# Battery-management.net
KiCad netlist of a schematic drawn in Altium Designer
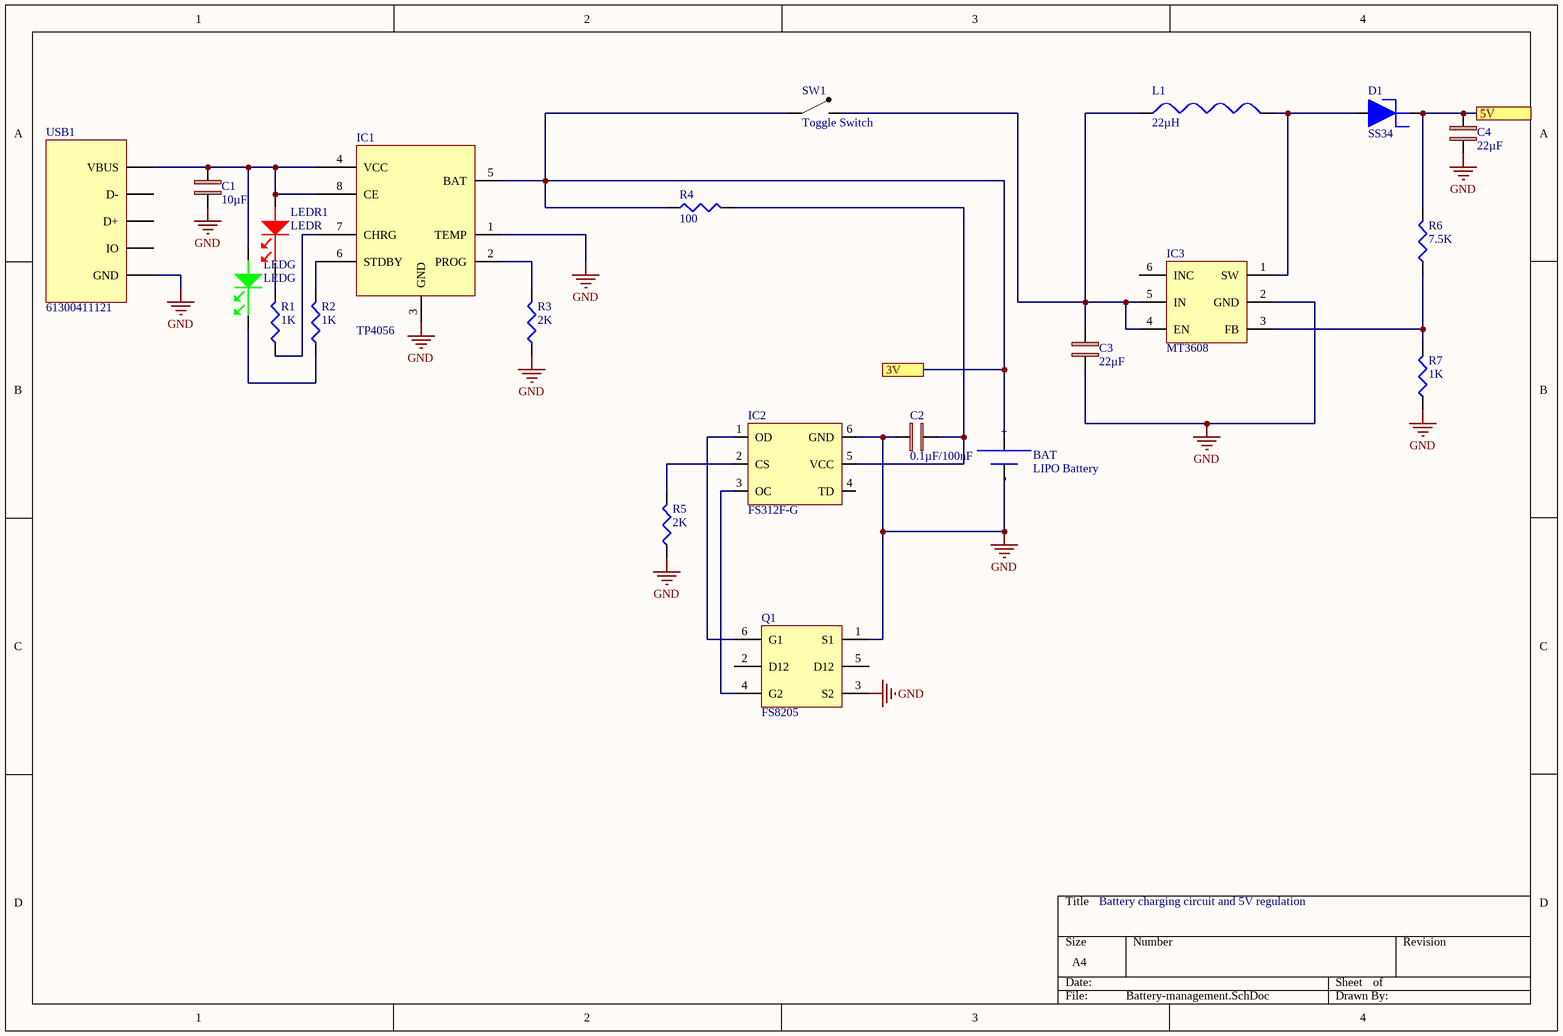
[diagram p0: Battery-management.SchDoc]

(export (version "E")
  (design (tool "Eeschema 10.0.6"))
  (components
    (comp (ref "BAT")
      (value "LIPO Battery")
      (footprint "LIPO battery pads")
      (libsource (lib "Tama_Schlib") (part "103040 LIPO battery"))
    )
    (comp (ref "C1")
      (value "10µF")
      (footprint "ELCO")
      (description "RUBYCON - 35TZV10M4X6.1 - KONDENSATOR, 10µF, 35V, RADIAL, SMD")
      (fields
        (field (name "MANUFACTURER") "Rubycon")
        (field (name "MANUFACTURER PART NUMBER") "35TZV10M4X6.1")
      )
      (libsource (lib "Tama_Schlib") (part "35TZV10M4X6.1"))
    )
    (comp (ref "C2")
      (value "0.1µF/100nF")
      (footprint "MC0603B104K250CT")
      (description "Cap Ceramic 0.1uF 25V X7R 10% Pad SMD 0603 125C T/R")
      (fields
        (field (name "MANUFACTURER") "Multicomp")
        (field (name "MANUFACTURER PART NUMBER") "MC0603B104K250CT")
      )
      (libsource (lib "Tama_Schlib") (part "MC0603B104K250CT"))
    )
    (comp (ref "C3")
      (value "22µF")
      (footprint "1210ZC226KAT2A")
      (description "1210 22 uF 10 V ±10 % Tolerance X7R Surface Mount Multilayer Ceramic Capacitor")
      (fields
        (field (name "MANUFACTURER") "Kyocera AVX")
        (field (name "MANUFACTURER PART NUMBER") "1210ZC226KAT2A")
      )
      (libsource (lib "Tama_Schlib") (part "1210ZC226KAT2A"))
    )
    (comp (ref "C4")
      (value "22µF")
      (footprint "1210ZC226KAT2A")
      (description "1210 22 uF 10 V ±10 % Tolerance X7R Surface Mount Multilayer Ceramic Capacitor")
      (fields
        (field (name "MANUFACTURER") "Kyocera AVX")
        (field (name "MANUFACTURER PART NUMBER") "1210ZC226KAT2A")
      )
      (libsource (lib "Tama_Schlib") (part "1210ZC226KAT2A"))
    )
    (comp (ref "D1")
      (value "SS34")
      (footprint "1N5822")
      (description "DIODE SCHOTTKY 40V 3A DO214AB")
      (fields
        (field (name "MANUFACTURER") "Vishay Semiconductors")
        (field (name "MANUFACTURER PART NUMBER") "SS34-E3/57T")
      )
      (libsource (lib "Tama_Schlib") (part "SS34-E3/57T"))
    )
    (comp (ref "IC1") (value "TP4056") (footprint "HSOP08") (libsource (lib "Tama_Schlib") (part "TP4056")))
    (comp (ref "IC2")
      (value "FS312F-G")
      (footprint "SOT95P280X145-6N")
      (description "Lithium battery protection IC")
      (libsource (lib "Tama_Schlib") (part "FS312F-G"))
    )
    (comp (ref "IC3")
      (value "MT3608")
      (footprint "SOT23-6")
      (description "Voltage regulator")
      (libsource (lib "Tama_Schlib") (part "MT3608"))
    )
    (comp (ref "L1")
      (value "22µH")
      (footprint "MLZ1608")
      (description "Inductor Power Shielded Multi-Layer 22uH 20% 2MHz Ferrite 0.05A 2.145Ohm DCR 0603 T/R")
      (fields
        (field (name "MANUFACTURER") "TDK")
        (field (name "MANUFACTURER PART NUMBER") "MLZ1608N220LT000")
      )
      (libsource (lib "Tama_Schlib") (part "MLZ1608N220LT000"))
    )
    (comp (ref "LEDG")
      (value "LEDG")
      (footprint "KPT-3216SGC")
      (description "LED Uni-Color SB. Green 565nm 2-Pin Chip LED T/R")
      (fields
        (field (name "MANUFACTURER") "Kingbright")
        (field (name "MANUFACTURER PART NUMBER") "KPT-3216SGC")
      )
      (libsource (lib "Tama_Schlib") (part "KPT-3216SGC"))
    )
    (comp (ref "LEDR1")
      (value "LEDR")
      (footprint "LSQ976-Z")
      (description "Led, SMD, Red, 180MCD, 633NM")
      (fields (field (name "MANUFACTURER") "Osram Opto") (field (name "MANUFACTURER PART NUMBER") "LSQ976-Z"))
      (libsource (lib "Tama_Schlib") (part "LSQ976-Z"))
    )
    (comp (ref "Q1")
      (value "FS8205")
      (footprint "SOT95P280X145-6N")
      (description "Dual N-Channel Enhancement Mode Power MOSFET")
      (libsource (lib "Tama_Schlib") (part "FS8205"))
    )
    (comp (ref "R1")
      (value "1K")
      (footprint "RK73H-0603")
      (description "1KΩ ±1% 1/8W ±100ppm/℃ 0603")
      (fields
        (field (name "MANUFACTURER") "KOA Speer")
        (field (name "MANUFACTURER PART NUMBER") "RK73H1JTTD1001F")
      )
      (libsource (lib "Tama_Schlib") (part "RK73H1JTTD1001F"))
    )
    (comp (ref "R2")
      (value "1K")
      (footprint "RK73H-0603")
      (description "1KΩ ±1% 1/8W ±100ppm/℃ 0603")
      (fields
        (field (name "MANUFACTURER") "KOA Speer")
        (field (name "MANUFACTURER PART NUMBER") "RK73H1JTTD1001F")
      )
      (libsource (lib "") (part "RK73H1JTTD1001F_1"))
    )
    (comp (ref "R3")
      (value "2K")
      (footprint "RC0603FR-072KL")
      (description "2000Ω ± 1.00% 0.1W ± 100ppm/℃ 0603")
      (fields
        (field (name "MANUFACTURER") "Yageo")
        (field (name "MANUFACTURER PART NUMBER") "RC0603FR-072KL")
      )
      (libsource (lib "Tama_Schlib") (part "RC0603FR-072KL"))
    )
    (comp (ref "R4")
      (value "100")
      (footprint "CRGP2512")
      (description "Res Thick Film 2512 100 Ohm 1% 2W ±100ppm/C Pad SMD T/R")
      (fields
        (field (name "MANUFACTURER") "TE Connectivity")
        (field (name "MANUFACTURER PART NUMBER") "CRGP2512F100R")
      )
      (libsource (lib "Tama_Schlib") (part "CRGP2512F100R"))
    )
    (comp (ref "R5")
      (value "2K")
      (footprint "RC0603FR-072KL")
      (description "2000Ω ± 1.00% 0.1W ± 100ppm/℃ 0603")
      (fields
        (field (name "MANUFACTURER") "Yageo")
        (field (name "MANUFACTURER PART NUMBER") "RC0603FR-072KL")
      )
      (libsource (lib "Tama_Schlib") (part "RC0603FR-072KL"))
    )
    (comp (ref "R6")
      (value "7.5K")
      (footprint "RC0603FR-072KL")
      (description "7500Ω ± 1.00% 0.1W ± 100ppm/℃ 0603")
      (fields
        (field (name "MANUFACTURER") "Yageo")
        (field (name "MANUFACTURER PART NUMBER") "RC0603FR-077K5L")
      )
      (libsource (lib "Tama_Schlib") (part "RC0603FR-077K5L"))
    )
    (comp (ref "R7")
      (value "1K")
      (footprint "RK73H-0603")
      (description "1KΩ ±1% 1/8W ±100ppm/℃ 0603")
      (fields
        (field (name "MANUFACTURER") "KOA Speer")
        (field (name "MANUFACTURER PART NUMBER") "RK73H1JTTD1001F")
      )
      (libsource (lib "Tama_Schlib") (part "RK73H1JTTD1001F"))
    )
    (comp (ref "SW1")
      (value "Toggle Switch")
      (footprint "SMD Switch")
      (description "C&K SK-12D07-VG 3 NS Switches > Slide > Miniature > Mini R/A Slide")
      (fields
        (field (name "MANUFACTURER") "ITT C&K")
        (field (name "MANUFACTURER PART NUMBER") "SK12D07VG3NS")
      )
      (libsource (lib "Tama_Schlib") (part "SK12D07VG3NS"))
    )
    (comp (ref "USB1")
      (value "61300411121")
      (footprint "Micro USB - Type B")
      (description "CONN HEADER 4 POS 2.54")
      (fields (field (name "MANUFACTURER") "Wurth Electronics"))
      (libsource (lib "Tama_Schlib") (part "61300411121"))
    )
  )
  (nets
    (net (code "1") (name "/3V") (class "Default")
      (node (ref "BAT") (pin "1") (pinfunction "+_1") (pintype "passive"))
      (node (ref "IC1") (pin "5") (pinfunction "BAT_5") (pintype "passive"))
      (node (ref "R4") (pin "2") (pinfunction "2_2") (pintype "passive"))
      (node (ref "SW1") (pin "1") (pinfunction "1_1") (pintype "passive"))
    )
    (net (code "2") (name "/5V") (class "Default")
      (node (ref "C4") (pin "1") (pinfunction "1_1") (pintype "passive"))
      (node (ref "D1") (pin "2") (pinfunction "2_2") (pintype "passive"))
      (node (ref "R6") (pin "2") (pinfunction "2_2") (pintype "passive"))
    )
    (net (code "3") (name "GND") (class "Default")
      (node (ref "BAT") (pin "2") (pinfunction "-_2") (pintype "passive"))
      (node (ref "C1") (pin "2") (pinfunction "2_2") (pintype "passive"))
      (node (ref "C2") (pin "2") (pinfunction "2_2") (pintype "passive"))
      (node (ref "C3") (pin "2") (pinfunction "2_2") (pintype "passive"))
      (node (ref "C4") (pin "2") (pinfunction "2_2") (pintype "passive"))
      (node (ref "IC1") (pin "1") (pinfunction "TEMP_1") (pintype "passive"))
      (node (ref "IC1") (pin "3") (pinfunction "GND_3") (pintype "passive"))
      (node (ref "IC2") (pin "6") (pinfunction "GND_6") (pintype "passive"))
      (node (ref "IC3") (pin "2") (pinfunction "GND_2") (pintype "passive"))
      (node (ref "Q1") (pin "1") (pinfunction "S1_1") (pintype "passive"))
      (node (ref "Q1") (pin "3") (pinfunction "S2_3") (pintype "passive"))
      (node (ref "R3") (pin "1") (pinfunction "1_1") (pintype "passive"))
      (node (ref "R5") (pin "1") (pinfunction "1_1") (pintype "passive"))
      (node (ref "R7") (pin "1") (pinfunction "1_1") (pintype "passive"))
      (node (ref "USB1") (pin "5") (pinfunction "GND_5") (pintype "passive"))
    )
    (net (code "4") (name "Net-(IC1-CE)") (class "Default")
      (node (ref "C1") (pin "1") (pinfunction "1_1") (pintype "passive"))
      (node (ref "IC1") (pin "4") (pinfunction "VCC_4") (pintype "passive"))
      (node (ref "IC1") (pin "8") (pinfunction "CE_8") (pintype "passive"))
      (node (ref "LEDG") (pin "1") (pinfunction "+_1") (pintype "passive"))
      (node (ref "LEDR1") (pin "1") (pinfunction "+_1") (pintype "passive"))
      (node (ref "USB1") (pin "1") (pinfunction "VBUS_1") (pintype "passive"))
    )
    (net (code "5") (name "Net-(IC1-CHRG)") (class "Default")
      (node (ref "IC1") (pin "7") (pinfunction "CHRG_7") (pintype "passive"))
      (node (ref "R1") (pin "1") (pinfunction "1_1") (pintype "passive"))
    )
    (net (code "6") (name "Net-(IC1-PROG)") (class "Default")
      (node (ref "IC1") (pin "2") (pinfunction "PROG_2") (pintype "passive"))
      (node (ref "R3") (pin "2") (pinfunction "2_2") (pintype "passive"))
    )
    (net (code "7") (name "Net-(IC1-STDBY)") (class "Default")
      (node (ref "IC1") (pin "6") (pinfunction "STDBY_6") (pintype "passive"))
      (node (ref "R2") (pin "1") (pinfunction "1_1") (pintype "passive"))
    )
    (net (code "8") (name "Net-(IC2-CS)") (class "Default")
      (node (ref "IC2") (pin "2") (pinfunction "CS_2") (pintype "passive"))
      (node (ref "R5") (pin "2") (pinfunction "2_2") (pintype "passive"))
    )
    (net (code "9") (name "Net-(IC2-OC)") (class "Default")
      (node (ref "IC2") (pin "3") (pinfunction "OC_3") (pintype "passive"))
      (node (ref "Q1") (pin "4") (pinfunction "G2_4") (pintype "passive"))
    )
    (net (code "10") (name "Net-(IC2-OD)") (class "Default")
      (node (ref "IC2") (pin "1") (pinfunction "OD_1") (pintype "passive"))
      (node (ref "Q1") (pin "6") (pinfunction "G1_6") (pintype "passive"))
    )
    (net (code "11") (name "Net-(IC2-VCC)") (class "Default")
      (node (ref "C2") (pin "1") (pinfunction "1_1") (pintype "passive"))
      (node (ref "IC2") (pin "5") (pinfunction "VCC_5") (pintype "passive"))
      (node (ref "R4") (pin "1") (pinfunction "1_1") (pintype "passive"))
    )
    (net (code "12") (name "Net-(IC3-EN)") (class "Default")
      (node (ref "C3") (pin "1") (pinfunction "1_1") (pintype "passive"))
      (node (ref "IC3") (pin "4") (pinfunction "EN_4") (pintype "passive"))
      (node (ref "IC3") (pin "5") (pinfunction "IN_5") (pintype "passive"))
      (node (ref "L1") (pin "1") (pinfunction "1_1") (pintype "passive"))
      (node (ref "SW1") (pin "2") (pinfunction "2_2") (pintype "passive"))
    )
    (net (code "13") (name "Net-(IC3-FB)") (class "Default")
      (node (ref "IC3") (pin "3") (pinfunction "FB_3") (pintype "passive"))
      (node (ref "R6") (pin "1") (pinfunction "1_1") (pintype "passive"))
      (node (ref "R7") (pin "2") (pinfunction "2_2") (pintype "passive"))
    )
    (net (code "14") (name "Net-(IC3-SW)") (class "Default")
      (node (ref "D1") (pin "1") (pinfunction "1_1") (pintype "passive"))
      (node (ref "IC3") (pin "1") (pinfunction "SW_1") (pintype "passive"))
      (node (ref "L1") (pin "2") (pinfunction "2_2") (pintype "passive"))
    )
    (net (code "15") (name "Net-(LEDG-Pad2)") (class "Default")
      (node (ref "LEDG") (pin "2") (pinfunction "2_2") (pintype "passive"))
      (node (ref "R2") (pin "2") (pinfunction "2_2") (pintype "passive"))
    )
    (net (code "16") (name "Net-(LEDR1-Pad2)") (class "Default")
      (node (ref "LEDR1") (pin "2") (pinfunction "2_2") (pintype "passive"))
      (node (ref "R1") (pin "2") (pinfunction "2_2") (pintype "passive"))
    )
    (net (code "17") (name "unconnected-(IC2-TD-Pad4)") (class "Default")
      (node (ref "IC2") (pin "4") (pinfunction "TD_4") (pintype "passive"))
    )
    (net (code "18") (name "unconnected-(IC3-INC-Pad6)") (class "Default")
      (node (ref "IC3") (pin "6") (pinfunction "INC_6") (pintype "passive"))
    )
    (net (code "19") (name "unconnected-(Q1-D12-Pad2)") (class "Default")
      (node (ref "Q1") (pin "2") (pinfunction "D12_2") (pintype "passive"))
    )
    (net (code "20") (name "unconnected-(Q1-D12-Pad5)") (class "Default")
      (node (ref "Q1") (pin "5") (pinfunction "D12_5") (pintype "passive"))
    )
    (net (code "21") (name "unconnected-(USB1-D+-Pad3)") (class "Default")
      (node (ref "USB1") (pin "3") (pinfunction "D+_3") (pintype "passive"))
    )
    (net (code "22") (name "unconnected-(USB1-D--Pad2)") (class "Default")
      (node (ref "USB1") (pin "2") (pinfunction "D-_2") (pintype "passive"))
    )
    (net (code "23") (name "unconnected-(USB1-IO-Pad4)") (class "Default")
      (node (ref "USB1") (pin "4") (pinfunction "IO_4") (pintype "passive"))
    )
  )
)
